# DSP_CNC.net
KiCad netlist of a schematic drawn in EAGLE
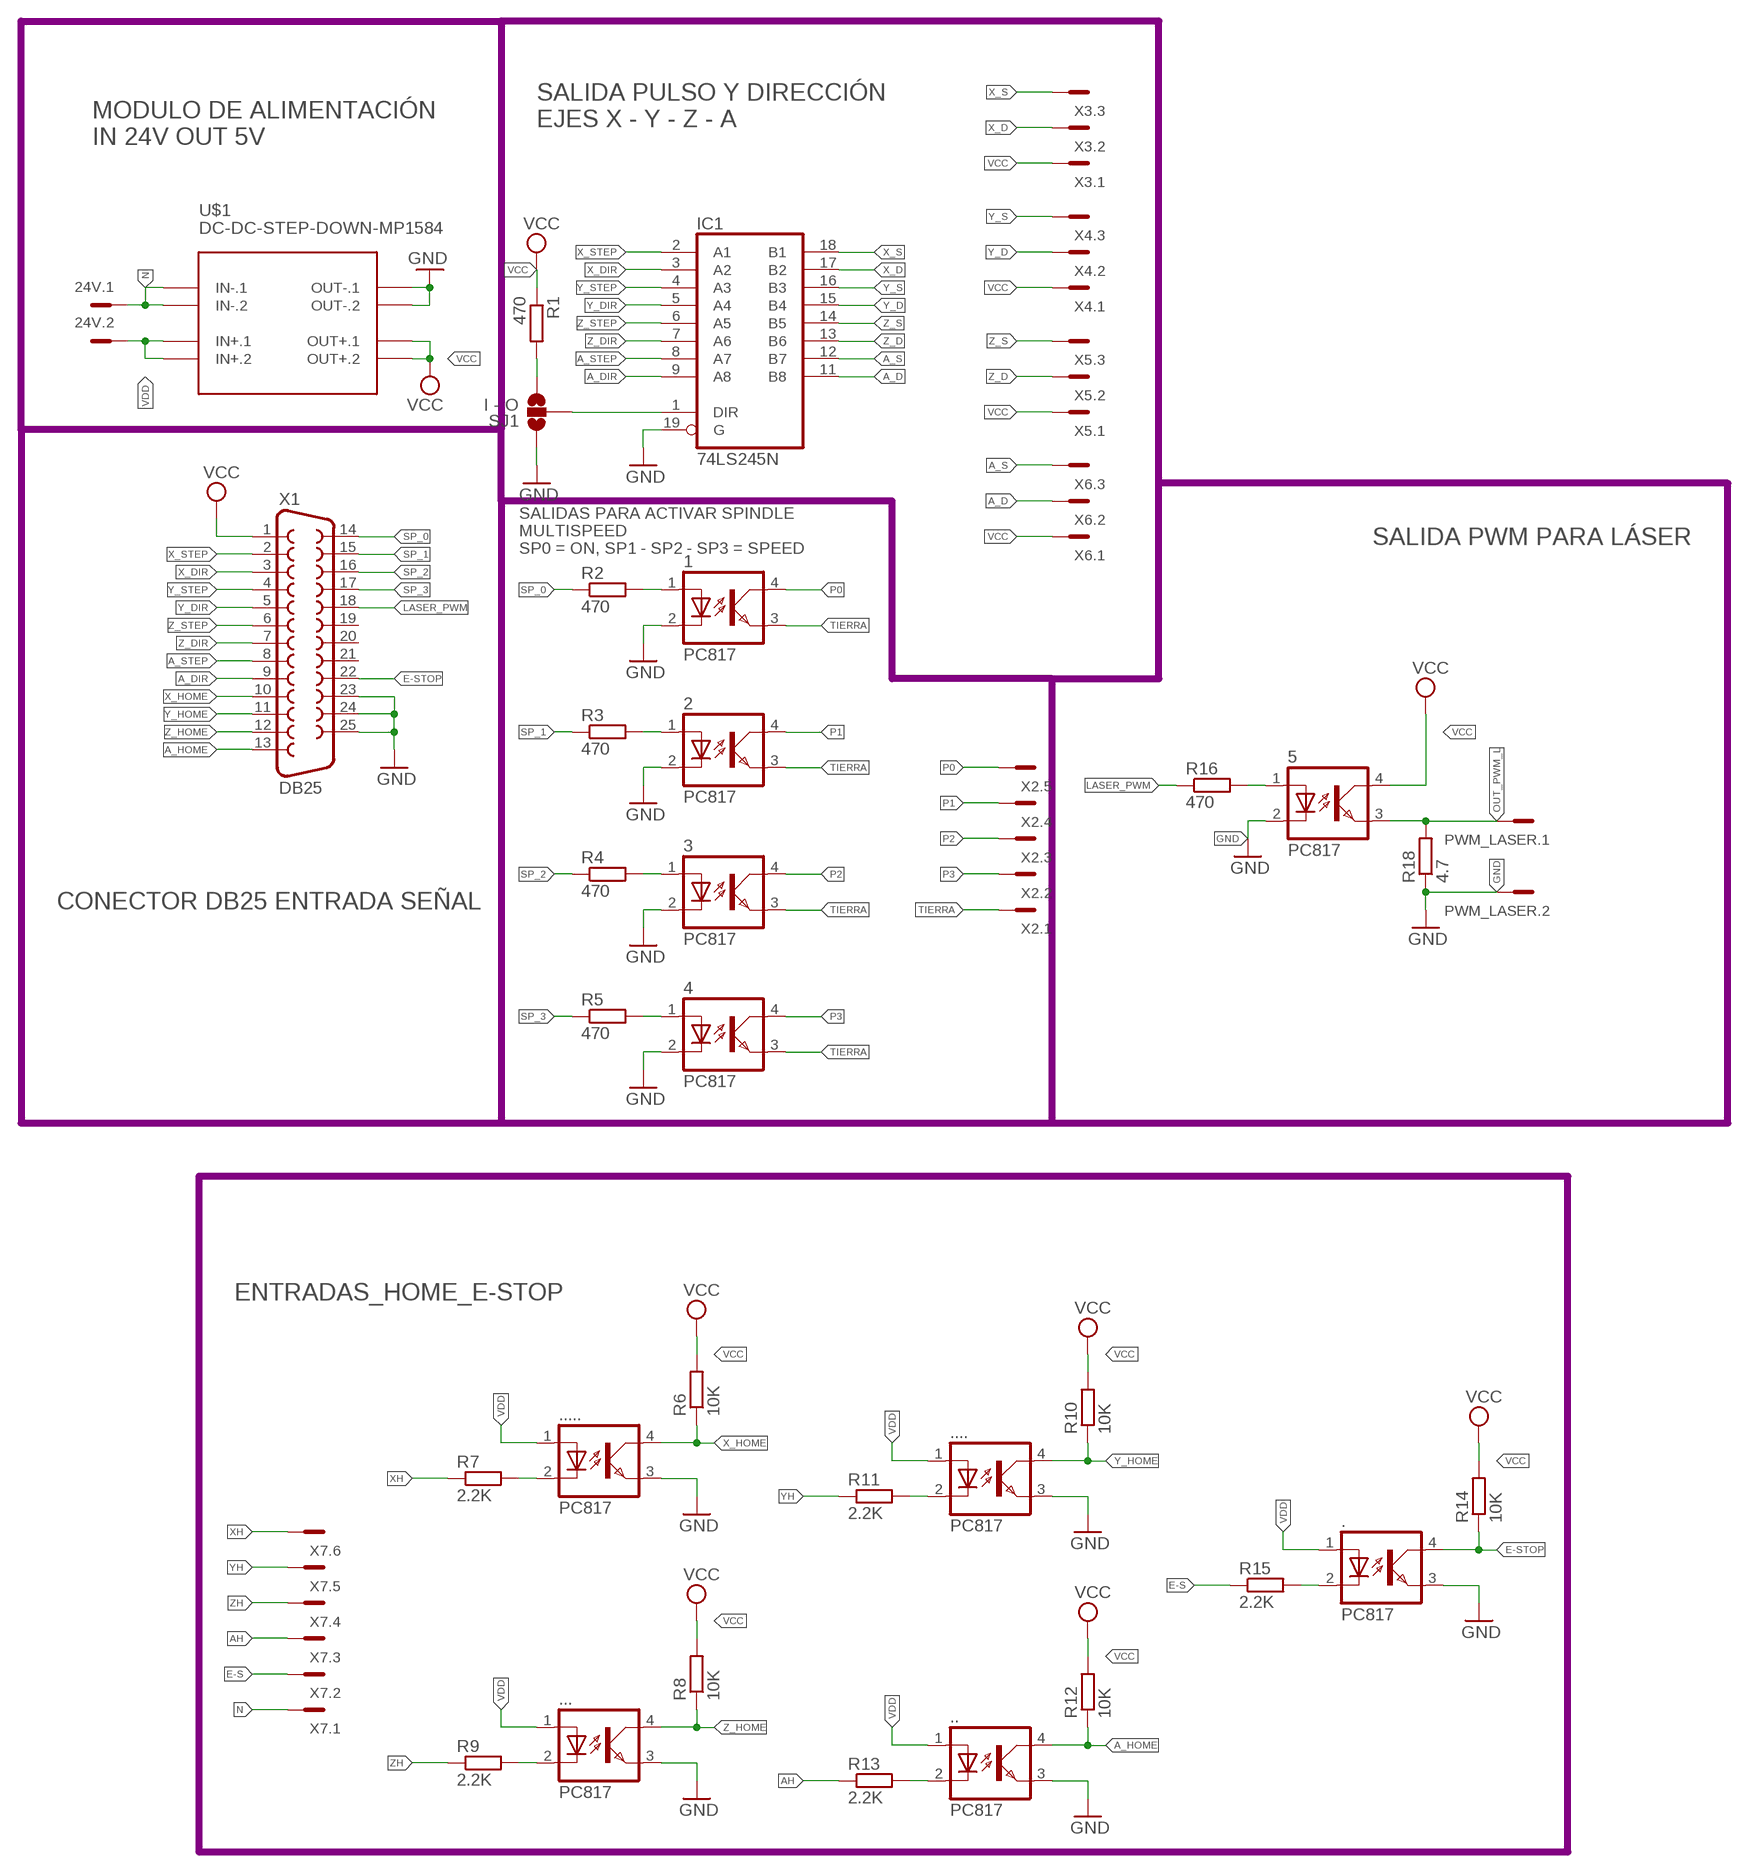
[diagram p0: schematic, sheet 1]

(export (version "E")
  (design (tool "Eeschema 10.0.6"))
  (components
    (comp (ref ".")
      (value "PC817")
      (footprint "eagle-import:DIL04")
      (libsource (lib "eagle-import") (part "PC817"))
    )
    (comp (ref "..")
      (value "PC817")
      (footprint "eagle-import:DIL04")
      (libsource (lib "eagle-import") (part "PC817"))
    )
    (comp (ref "...")
      (value "PC817")
      (footprint "eagle-import:DIL04")
      (libsource (lib "eagle-import") (part "PC817"))
    )
    (comp (ref "....")
      (value "PC817")
      (footprint "eagle-import:DIL04")
      (libsource (lib "eagle-import") (part "PC817"))
    )
    (comp (ref ".....")
      (value "PC817")
      (footprint "eagle-import:DIL04")
      (libsource (lib "eagle-import") (part "PC817"))
    )
    (comp (ref "1")
      (value "PC817")
      (footprint "eagle-import:DIL04")
      (libsource (lib "eagle-import") (part "PC817"))
    )
    (comp (ref "2")
      (value "PC817")
      (footprint "eagle-import:DIL04")
      (libsource (lib "eagle-import") (part "PC817"))
    )
    (comp (ref "3")
      (value "PC817")
      (footprint "eagle-import:DIL04")
      (libsource (lib "eagle-import") (part "PC817"))
    )
    (comp (ref "4")
      (value "PC817")
      (footprint "eagle-import:DIL04")
      (libsource (lib "eagle-import") (part "PC817"))
    )
    (comp (ref "5")
      (value "PC817")
      (footprint "eagle-import:DIL04")
      (libsource (lib "eagle-import") (part "PC817"))
    )
    (comp (ref "24V")
      (value "MCV2")
      (footprint "eagle-import:MCV2")
      (libsource (lib "eagle-import") (part "MCV2"))
    )
    (comp (ref "IC1")
      (value "74LS245N")
      (footprint "eagle-import:DIL20")
      (libsource (lib "eagle-import") (part "74245NLS"))
    )
    (comp (ref "PWM_LASER")
      (value "MCV2")
      (footprint "eagle-import:MCV2")
      (libsource (lib "eagle-import") (part "MCV2"))
    )
    (comp (ref "R1")
      (value "470")
      (footprint "eagle-import:0207_10")
      (libsource (lib "eagle-import") (part "R-EU_0207/10"))
    )
    (comp (ref "R2")
      (value "470")
      (footprint "eagle-import:0207_10")
      (libsource (lib "eagle-import") (part "R-EU_0207/10"))
    )
    (comp (ref "R3")
      (value "470")
      (footprint "eagle-import:0207_10")
      (libsource (lib "eagle-import") (part "R-EU_0207/10"))
    )
    (comp (ref "R4")
      (value "470")
      (footprint "eagle-import:0207_10")
      (libsource (lib "eagle-import") (part "R-EU_0207/10"))
    )
    (comp (ref "R5")
      (value "470")
      (footprint "eagle-import:0207_10")
      (libsource (lib "eagle-import") (part "R-EU_0207/10"))
    )
    (comp (ref "R6")
      (value "10K")
      (footprint "eagle-import:0207_10")
      (libsource (lib "eagle-import") (part "R-EU_0207/10"))
    )
    (comp (ref "R7")
      (value "2.2K")
      (footprint "eagle-import:0207_10")
      (libsource (lib "eagle-import") (part "R-EU_0207/10"))
    )
    (comp (ref "R8")
      (value "10K")
      (footprint "eagle-import:0207_10")
      (libsource (lib "eagle-import") (part "R-EU_0207/10"))
    )
    (comp (ref "R9")
      (value "2.2K")
      (footprint "eagle-import:0207_10")
      (libsource (lib "eagle-import") (part "R-EU_0207/10"))
    )
    (comp (ref "R10")
      (value "10K")
      (footprint "eagle-import:0207_10")
      (libsource (lib "eagle-import") (part "R-EU_0207/10"))
    )
    (comp (ref "R11")
      (value "2.2K")
      (footprint "eagle-import:0207_10")
      (libsource (lib "eagle-import") (part "R-EU_0207/10"))
    )
    (comp (ref "R12")
      (value "10K")
      (footprint "eagle-import:0207_10")
      (libsource (lib "eagle-import") (part "R-EU_0207/10"))
    )
    (comp (ref "R13")
      (value "2.2K")
      (footprint "eagle-import:0207_10")
      (libsource (lib "eagle-import") (part "R-EU_0207/10"))
    )
    (comp (ref "R14")
      (value "10K")
      (footprint "eagle-import:0207_10")
      (libsource (lib "eagle-import") (part "R-EU_0207/10"))
    )
    (comp (ref "R15")
      (value "2.2K")
      (footprint "eagle-import:0207_10")
      (libsource (lib "eagle-import") (part "R-EU_0207/10"))
    )
    (comp (ref "R16")
      (value "470")
      (footprint "eagle-import:0207_10")
      (libsource (lib "eagle-import") (part "R-EU_0207/10"))
    )
    (comp (ref "R18")
      (value "4.7")
      (footprint "eagle-import:0207_10")
      (libsource (lib "eagle-import") (part "R-EU_0207/10"))
    )
    (comp (ref "SJ1")
      (value "I - O")
      (footprint "eagle-import:SJ_2W")
      (libsource (lib "eagle-import") (part "SOLDERJUMPER_2WAY-OLDW"))
    )
    (comp (ref "U$1")
      (value "DC-DC-STEP-DOWN-MP1584")
      (footprint "eagle-import:DC-DC-STEP-DOWN-MP1584")
      (libsource (lib "eagle-import") (part "DC-DC-STEP-DOWN-MP1584"))
    )
    (comp (ref "X1")
      (value "DB25")
      (footprint "eagle-import:F25HP")
      (libsource (lib "eagle-import") (part "F25HP"))
    )
    (comp (ref "X2")
      (value "SPINDLE ON - SP123")
      (footprint "eagle-import:MCV5")
      (libsource (lib "eagle-import") (part "MCV5"))
    )
    (comp (ref "X3")
      (value "EJE_X")
      (footprint "eagle-import:MCV3")
      (libsource (lib "eagle-import") (part "MCV3"))
    )
    (comp (ref "X4")
      (value "EJE_Y")
      (footprint "eagle-import:MCV3")
      (libsource (lib "eagle-import") (part "MCV3"))
    )
    (comp (ref "X5")
      (value "EJE_Z")
      (footprint "eagle-import:MCV3")
      (libsource (lib "eagle-import") (part "MCV3"))
    )
    (comp (ref "X6")
      (value "EJE_A")
      (footprint "eagle-import:MCV3")
      (libsource (lib "eagle-import") (part "MCV3"))
    )
    (comp (ref "X7")
      (value "INPUT_HOME_E-STOP")
      (footprint "eagle-import:MCV6")
      (libsource (lib "eagle-import") (part "MCV6"))
    )
  )
  (nets
    (net (code "1") (name "AH") (class "Default")
      (node (ref "R13") (pin "1") (pinfunction "1_1") (pintype "passive"))
      (node (ref "X7") (pin "3") (pinfunction "SK_3") (pintype "passive"))
    )
    (net (code "2") (name "A_D") (class "Default")
      (node (ref "IC1") (pin "11") (pinfunction "B8_11") (pintype "bidirectional"))
      (node (ref "X6") (pin "2") (pinfunction "SK_2") (pintype "passive"))
    )
    (net (code "3") (name "A_DIR") (class "Default")
      (node (ref "IC1") (pin "9") (pinfunction "A8_9") (pintype "bidirectional"))
      (node (ref "X1") (pin "9") (pinfunction "9_9") (pintype "passive"))
    )
    (net (code "4") (name "A_HOME") (class "Default")
      (node (ref "..") (pin "4") (pinfunction "COL_4") (pintype "passive"))
      (node (ref "R12") (pin "1") (pinfunction "1_1") (pintype "passive"))
      (node (ref "X1") (pin "13") (pinfunction "13_13") (pintype "passive"))
    )
    (net (code "5") (name "A_S") (class "Default")
      (node (ref "IC1") (pin "12") (pinfunction "B7_12") (pintype "bidirectional"))
      (node (ref "X6") (pin "3") (pinfunction "SK_3") (pintype "passive"))
    )
    (net (code "6") (name "A_STEP") (class "Default")
      (node (ref "IC1") (pin "8") (pinfunction "A7_8") (pintype "bidirectional"))
      (node (ref "X1") (pin "8") (pinfunction "8_8") (pintype "passive"))
    )
    (net (code "7") (name "E-S") (class "Default")
      (node (ref "R15") (pin "1") (pinfunction "1_1") (pintype "passive"))
      (node (ref "X7") (pin "2") (pinfunction "SK_2") (pintype "passive"))
    )
    (net (code "8") (name "E-STOP") (class "Default")
      (node (ref ".") (pin "4") (pinfunction "COL_4") (pintype "passive"))
      (node (ref "R14") (pin "1") (pinfunction "1_1") (pintype "passive"))
      (node (ref "X1") (pin "22") (pinfunction "22_22") (pintype "passive"))
    )
    (net (code "9") (name "GND") (class "Default")
      (node (ref ".") (pin "3") (pinfunction "EMIT_3") (pintype "passive"))
      (node (ref "..") (pin "3") (pinfunction "EMIT_3") (pintype "passive"))
      (node (ref "...") (pin "3") (pinfunction "EMIT_3") (pintype "passive"))
      (node (ref "....") (pin "3") (pinfunction "EMIT_3") (pintype "passive"))
      (node (ref ".....") (pin "3") (pinfunction "EMIT_3") (pintype "passive"))
      (node (ref "1") (pin "2") (pinfunction "C_2") (pintype "passive"))
      (node (ref "2") (pin "2") (pinfunction "C_2") (pintype "passive"))
      (node (ref "3") (pin "2") (pinfunction "C_2") (pintype "passive"))
      (node (ref "4") (pin "2") (pinfunction "C_2") (pintype "passive"))
      (node (ref "5") (pin "2") (pinfunction "C_2") (pintype "passive"))
      (node (ref "IC1") (pin "19") (pinfunction "G_19") (pintype "input"))
      (node (ref "PWM_LASER") (pin "2") (pinfunction "SK_2") (pintype "passive"))
      (node (ref "R18") (pin "1") (pinfunction "1_1") (pintype "passive"))
      (node (ref "SJ1") (pin "1") (pinfunction "1_1") (pintype "passive"))
      (node (ref "U$1") (pin "OUT-.1") (pinfunction "OUT-.1_OUT-.1") (pintype "bidirectional"))
      (node (ref "U$1") (pin "OUT-.2") (pinfunction "OUT-.2_OUT-.2") (pintype "bidirectional"))
      (node (ref "X1") (pin "23") (pinfunction "23_23") (pintype "passive"))
      (node (ref "X1") (pin "24") (pinfunction "24_24") (pintype "passive"))
      (node (ref "X1") (pin "25") (pinfunction "25_25") (pintype "passive"))
    )
    (net (code "10") (name "LASER_PWM") (class "Default")
      (node (ref "R16") (pin "1") (pinfunction "1_1") (pintype "passive"))
      (node (ref "X1") (pin "18") (pinfunction "18_18") (pintype "passive"))
    )
    (net (code "11") (name "N") (class "Default")
      (node (ref "24V") (pin "1") (pinfunction "SK_1") (pintype "passive"))
      (node (ref "U$1") (pin "IN-.1") (pinfunction "IN-.1_IN-.1") (pintype "bidirectional"))
      (node (ref "U$1") (pin "IN-.2") (pinfunction "IN-.2_IN-.2") (pintype "bidirectional"))
      (node (ref "X7") (pin "1") (pinfunction "SK_1") (pintype "passive"))
    )
    (net (code "12") (name "Net-(.-C)") (class "Default")
      (node (ref ".") (pin "2") (pinfunction "C_2") (pintype "passive"))
      (node (ref "R15") (pin "2") (pinfunction "2_2") (pintype "passive"))
    )
    (net (code "13") (name "Net-(..-C)") (class "Default")
      (node (ref "..") (pin "2") (pinfunction "C_2") (pintype "passive"))
      (node (ref "R13") (pin "2") (pinfunction "2_2") (pintype "passive"))
    )
    (net (code "14") (name "Net-(...-C)") (class "Default")
      (node (ref "...") (pin "2") (pinfunction "C_2") (pintype "passive"))
      (node (ref "R9") (pin "2") (pinfunction "2_2") (pintype "passive"))
    )
    (net (code "15") (name "Net-(....-C)") (class "Default")
      (node (ref "....") (pin "2") (pinfunction "C_2") (pintype "passive"))
      (node (ref "R11") (pin "2") (pinfunction "2_2") (pintype "passive"))
    )
    (net (code "16") (name "Net-(.....-C)") (class "Default")
      (node (ref ".....") (pin "2") (pinfunction "C_2") (pintype "passive"))
      (node (ref "R7") (pin "2") (pinfunction "2_2") (pintype "passive"))
    )
    (net (code "17") (name "Net-(1-A)") (class "Default")
      (node (ref "1") (pin "1") (pinfunction "A_1") (pintype "passive"))
      (node (ref "R2") (pin "2") (pinfunction "2_2") (pintype "passive"))
    )
    (net (code "18") (name "Net-(2-A)") (class "Default")
      (node (ref "2") (pin "1") (pinfunction "A_1") (pintype "passive"))
      (node (ref "R3") (pin "2") (pinfunction "2_2") (pintype "passive"))
    )
    (net (code "19") (name "Net-(3-A)") (class "Default")
      (node (ref "3") (pin "1") (pinfunction "A_1") (pintype "passive"))
      (node (ref "R4") (pin "2") (pinfunction "2_2") (pintype "passive"))
    )
    (net (code "20") (name "Net-(4-A)") (class "Default")
      (node (ref "4") (pin "1") (pinfunction "A_1") (pintype "passive"))
      (node (ref "R5") (pin "2") (pinfunction "2_2") (pintype "passive"))
    )
    (net (code "21") (name "Net-(5-A)") (class "Default")
      (node (ref "5") (pin "1") (pinfunction "A_1") (pintype "passive"))
      (node (ref "R16") (pin "2") (pinfunction "2_2") (pintype "passive"))
    )
    (net (code "22") (name "Net-(IC1A-DIR)") (class "Default")
      (node (ref "IC1") (pin "1") (pinfunction "DIR_1") (pintype "input"))
      (node (ref "SJ1") (pin "2") (pinfunction "2_2") (pintype "passive"))
    )
    (net (code "23") (name "Net-(R1-Pad2)") (class "Default")
      (node (ref "R1") (pin "2") (pinfunction "2_2") (pintype "passive"))
      (node (ref "SJ1") (pin "3") (pinfunction "3_3") (pintype "passive"))
    )
    (net (code "24") (name "OUT_PWM_L") (class "Default")
      (node (ref "5") (pin "3") (pinfunction "EMIT_3") (pintype "passive"))
      (node (ref "PWM_LASER") (pin "1") (pinfunction "SK_1") (pintype "passive"))
      (node (ref "R18") (pin "2") (pinfunction "2_2") (pintype "passive"))
    )
    (net (code "25") (name "P0") (class "Default")
      (node (ref "1") (pin "4") (pinfunction "COL_4") (pintype "passive"))
      (node (ref "X2") (pin "5") (pinfunction "SK_5") (pintype "passive"))
    )
    (net (code "26") (name "P1") (class "Default")
      (node (ref "2") (pin "4") (pinfunction "COL_4") (pintype "passive"))
      (node (ref "X2") (pin "4") (pinfunction "SK_4") (pintype "passive"))
    )
    (net (code "27") (name "P2") (class "Default")
      (node (ref "3") (pin "4") (pinfunction "COL_4") (pintype "passive"))
      (node (ref "X2") (pin "3") (pinfunction "SK_3") (pintype "passive"))
    )
    (net (code "28") (name "P3") (class "Default")
      (node (ref "4") (pin "4") (pinfunction "COL_4") (pintype "passive"))
      (node (ref "X2") (pin "2") (pinfunction "SK_2") (pintype "passive"))
    )
    (net (code "29") (name "SP_0") (class "Default")
      (node (ref "R2") (pin "1") (pinfunction "1_1") (pintype "passive"))
      (node (ref "X1") (pin "14") (pinfunction "14_14") (pintype "passive"))
    )
    (net (code "30") (name "SP_1") (class "Default")
      (node (ref "R3") (pin "1") (pinfunction "1_1") (pintype "passive"))
      (node (ref "X1") (pin "15") (pinfunction "15_15") (pintype "passive"))
    )
    (net (code "31") (name "SP_2") (class "Default")
      (node (ref "R4") (pin "1") (pinfunction "1_1") (pintype "passive"))
      (node (ref "X1") (pin "16") (pinfunction "16_16") (pintype "passive"))
    )
    (net (code "32") (name "SP_3") (class "Default")
      (node (ref "R5") (pin "1") (pinfunction "1_1") (pintype "passive"))
      (node (ref "X1") (pin "17") (pinfunction "17_17") (pintype "passive"))
    )
    (net (code "33") (name "TIERRA") (class "Default")
      (node (ref "1") (pin "3") (pinfunction "EMIT_3") (pintype "passive"))
      (node (ref "2") (pin "3") (pinfunction "EMIT_3") (pintype "passive"))
      (node (ref "3") (pin "3") (pinfunction "EMIT_3") (pintype "passive"))
      (node (ref "4") (pin "3") (pinfunction "EMIT_3") (pintype "passive"))
      (node (ref "X2") (pin "1") (pinfunction "SK_1") (pintype "passive"))
    )
    (net (code "34") (name "VCC") (class "Default")
      (node (ref "5") (pin "4") (pinfunction "COL_4") (pintype "passive"))
      (node (ref "R1") (pin "1") (pinfunction "1_1") (pintype "passive"))
      (node (ref "R10") (pin "2") (pinfunction "2_2") (pintype "passive"))
      (node (ref "R12") (pin "2") (pinfunction "2_2") (pintype "passive"))
      (node (ref "R14") (pin "2") (pinfunction "2_2") (pintype "passive"))
      (node (ref "R6") (pin "2") (pinfunction "2_2") (pintype "passive"))
      (node (ref "R8") (pin "2") (pinfunction "2_2") (pintype "passive"))
      (node (ref "U$1") (pin "OUT+.1") (pinfunction "OUT+.1_OUT+.1") (pintype "bidirectional"))
      (node (ref "U$1") (pin "OUT+.2") (pinfunction "OUT+.2_OUT+.2") (pintype "bidirectional"))
      (node (ref "X1") (pin "1") (pinfunction "1_1") (pintype "passive"))
      (node (ref "X3") (pin "1") (pinfunction "SK_1") (pintype "passive"))
      (node (ref "X4") (pin "1") (pinfunction "SK_1") (pintype "passive"))
      (node (ref "X5") (pin "1") (pinfunction "SK_1") (pintype "passive"))
      (node (ref "X6") (pin "1") (pinfunction "SK_1") (pintype "passive"))
    )
    (net (code "35") (name "VDD") (class "Default")
      (node (ref ".") (pin "1") (pinfunction "A_1") (pintype "passive"))
      (node (ref "..") (pin "1") (pinfunction "A_1") (pintype "passive"))
      (node (ref "...") (pin "1") (pinfunction "A_1") (pintype "passive"))
      (node (ref "....") (pin "1") (pinfunction "A_1") (pintype "passive"))
      (node (ref ".....") (pin "1") (pinfunction "A_1") (pintype "passive"))
      (node (ref "24V") (pin "2") (pinfunction "SK_2") (pintype "passive"))
      (node (ref "U$1") (pin "IN+.1") (pinfunction "IN+.1_IN+.1") (pintype "bidirectional"))
      (node (ref "U$1") (pin "IN+.2") (pinfunction "IN+.2_IN+.2") (pintype "bidirectional"))
    )
    (net (code "36") (name "XH") (class "Default")
      (node (ref "R7") (pin "1") (pinfunction "1_1") (pintype "passive"))
      (node (ref "X7") (pin "6") (pinfunction "SK_6") (pintype "passive"))
    )
    (net (code "37") (name "X_D") (class "Default")
      (node (ref "IC1") (pin "17") (pinfunction "B2_17") (pintype "bidirectional"))
      (node (ref "X3") (pin "2") (pinfunction "SK_2") (pintype "passive"))
    )
    (net (code "38") (name "X_DIR") (class "Default")
      (node (ref "IC1") (pin "3") (pinfunction "A2_3") (pintype "bidirectional"))
      (node (ref "X1") (pin "3") (pinfunction "3_3") (pintype "passive"))
    )
    (net (code "39") (name "X_HOME") (class "Default")
      (node (ref ".....") (pin "4") (pinfunction "COL_4") (pintype "passive"))
      (node (ref "R6") (pin "1") (pinfunction "1_1") (pintype "passive"))
      (node (ref "X1") (pin "10") (pinfunction "10_10") (pintype "passive"))
    )
    (net (code "40") (name "X_S") (class "Default")
      (node (ref "IC1") (pin "18") (pinfunction "B1_18") (pintype "bidirectional"))
      (node (ref "X3") (pin "3") (pinfunction "SK_3") (pintype "passive"))
    )
    (net (code "41") (name "X_STEP") (class "Default")
      (node (ref "IC1") (pin "2") (pinfunction "A1_2") (pintype "bidirectional"))
      (node (ref "X1") (pin "2") (pinfunction "2_2") (pintype "passive"))
    )
    (net (code "42") (name "YH") (class "Default")
      (node (ref "R11") (pin "1") (pinfunction "1_1") (pintype "passive"))
      (node (ref "X7") (pin "5") (pinfunction "SK_5") (pintype "passive"))
    )
    (net (code "43") (name "Y_D") (class "Default")
      (node (ref "IC1") (pin "15") (pinfunction "B4_15") (pintype "bidirectional"))
      (node (ref "X4") (pin "2") (pinfunction "SK_2") (pintype "passive"))
    )
    (net (code "44") (name "Y_DIR") (class "Default")
      (node (ref "IC1") (pin "5") (pinfunction "A4_5") (pintype "bidirectional"))
      (node (ref "X1") (pin "5") (pinfunction "5_5") (pintype "passive"))
    )
    (net (code "45") (name "Y_HOME") (class "Default")
      (node (ref "....") (pin "4") (pinfunction "COL_4") (pintype "passive"))
      (node (ref "R10") (pin "1") (pinfunction "1_1") (pintype "passive"))
      (node (ref "X1") (pin "11") (pinfunction "11_11") (pintype "passive"))
    )
    (net (code "46") (name "Y_S") (class "Default")
      (node (ref "IC1") (pin "16") (pinfunction "B3_16") (pintype "bidirectional"))
      (node (ref "X4") (pin "3") (pinfunction "SK_3") (pintype "passive"))
    )
    (net (code "47") (name "Y_STEP") (class "Default")
      (node (ref "IC1") (pin "4") (pinfunction "A3_4") (pintype "bidirectional"))
      (node (ref "X1") (pin "4") (pinfunction "4_4") (pintype "passive"))
    )
    (net (code "48") (name "ZH") (class "Default")
      (node (ref "R9") (pin "1") (pinfunction "1_1") (pintype "passive"))
      (node (ref "X7") (pin "4") (pinfunction "SK_4") (pintype "passive"))
    )
    (net (code "49") (name "Z_D") (class "Default")
      (node (ref "IC1") (pin "13") (pinfunction "B6_13") (pintype "bidirectional"))
      (node (ref "X5") (pin "2") (pinfunction "SK_2") (pintype "passive"))
    )
    (net (code "50") (name "Z_DIR") (class "Default")
      (node (ref "IC1") (pin "7") (pinfunction "A6_7") (pintype "bidirectional"))
      (node (ref "X1") (pin "7") (pinfunction "7_7") (pintype "passive"))
    )
    (net (code "51") (name "Z_HOME") (class "Default")
      (node (ref "...") (pin "4") (pinfunction "COL_4") (pintype "passive"))
      (node (ref "R8") (pin "1") (pinfunction "1_1") (pintype "passive"))
      (node (ref "X1") (pin "12") (pinfunction "12_12") (pintype "passive"))
    )
    (net (code "52") (name "Z_S") (class "Default")
      (node (ref "IC1") (pin "14") (pinfunction "B5_14") (pintype "bidirectional"))
      (node (ref "X5") (pin "3") (pinfunction "SK_3") (pintype "passive"))
    )
    (net (code "53") (name "Z_STEP") (class "Default")
      (node (ref "IC1") (pin "6") (pinfunction "A5_6") (pintype "bidirectional"))
      (node (ref "X1") (pin "6") (pinfunction "6_6") (pintype "passive"))
    )
    (net (code "54") (name "unconnected-(X1-Pad19)") (class "Default")
      (node (ref "X1") (pin "19") (pinfunction "19_19") (pintype "passive"))
    )
    (net (code "55") (name "unconnected-(X1-Pad20)") (class "Default")
      (node (ref "X1") (pin "20") (pinfunction "20_20") (pintype "passive"))
    )
    (net (code "56") (name "unconnected-(X1-Pad21)") (class "Default")
      (node (ref "X1") (pin "21") (pinfunction "21_21") (pintype "passive"))
    )
  )
)
